# loiterboard.net
KiCad netlist of a schematic drawn in EAGLE
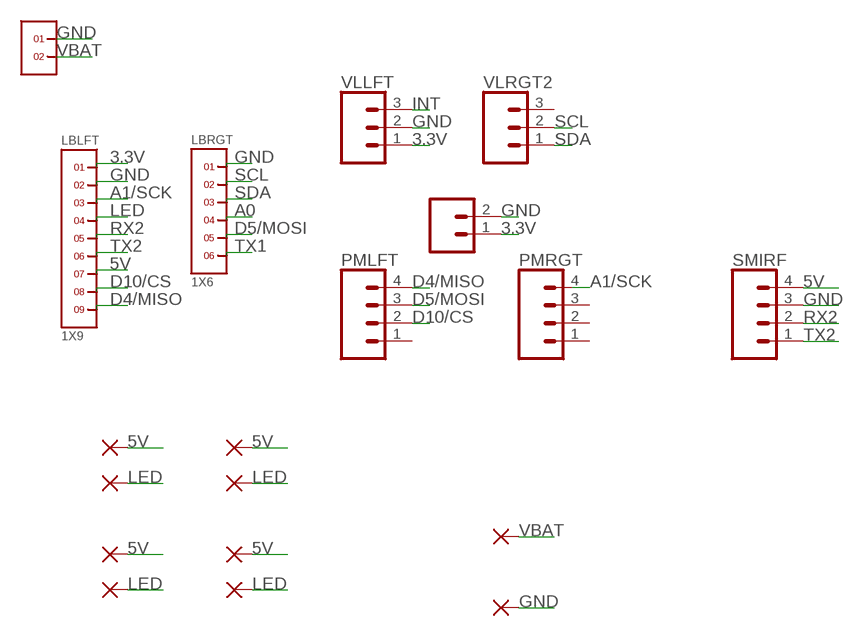
[diagram p0: schematic, sheet 1]

(export (version "E")
  (design (tool "Eeschema 10.0.6"))
  (components
    (comp (ref "LBLFT")
      (value "1X9")
      (footprint "eagle-import:1X9")
      (libsource (lib "eagle-import") (part "1X9"))
    )
    (comp (ref "LBRGT")
      (value "1X6")
      (footprint "eagle-import:1X6")
      (libsource (lib "eagle-import") (part "1X6"))
    )
    (comp (ref "PAD1")
      (value "SMD2")
      (footprint "eagle-import:SMD1,27-2,54")
      (libsource (lib "eagle-import") (part "SMD2"))
    )
    (comp (ref "PAD2")
      (value "SMD2")
      (footprint "eagle-import:SMD1,27-2,54")
      (libsource (lib "eagle-import") (part "SMD2"))
    )
    (comp (ref "PAD3")
      (value "SMD2")
      (footprint "eagle-import:SMD1,27-2,54")
      (libsource (lib "eagle-import") (part "SMD2"))
    )
    (comp (ref "PAD4")
      (value "SMD2")
      (footprint "eagle-import:SMD1,27-2,54")
      (libsource (lib "eagle-import") (part "SMD2"))
    )
    (comp (ref "PAD5")
      (value "SMD2")
      (footprint "eagle-import:SMD1,27-2,54")
      (libsource (lib "eagle-import") (part "SMD2"))
    )
    (comp (ref "PAD6")
      (value "LED")
      (footprint "eagle-import:SMD1,27-2,54")
      (libsource (lib "eagle-import") (part "SMD2"))
    )
    (comp (ref "PAD7")
      (value "SMD2")
      (footprint "eagle-import:SMD1,27-2,54")
      (libsource (lib "eagle-import") (part "SMD2"))
    )
    (comp (ref "PAD8")
      (value "SMD2")
      (footprint "eagle-import:SMD1,27-2,54")
      (libsource (lib "eagle-import") (part "SMD2"))
    )
    (comp (ref "PAD9")
      (value "SMD2")
      (footprint "eagle-import:SMD1,27-2,54")
      (libsource (lib "eagle-import") (part "SMD2"))
    )
    (comp (ref "PAD10")
      (value "SMD2")
      (footprint "eagle-import:SMD1,27-2,54")
      (libsource (lib "eagle-import") (part "SMD2"))
    )
    (comp (ref "PMLFT")
      (value "CONN_04")
      (footprint "eagle-import:1X04")
      (libsource (lib "eagle-import") (part "CONN_04"))
    )
    (comp (ref "PMRGT")
      (value "CONN_04")
      (footprint "eagle-import:1X04")
      (libsource (lib "eagle-import") (part "CONN_04"))
    )
    (comp (ref "PWPWR")
      (value "CONN_02")
      (footprint "eagle-import:1X02")
      (libsource (lib "eagle-import") (part "CONN_02"))
    )
    (comp (ref "SMIRF")
      (value "CONN_04")
      (footprint "eagle-import:1X04")
      (libsource (lib "eagle-import") (part "CONN_04"))
    )
    (comp (ref "U$1")
      (value "1X2")
      (footprint "eagle-import:1X2")
      (libsource (lib "eagle-import") (part "1X2"))
    )
    (comp (ref "VLLFT")
      (value "CONN_03")
      (footprint "eagle-import:1X03")
      (libsource (lib "eagle-import") (part "CONN_03"))
    )
    (comp (ref "VLRGT2")
      (value "CONN_03")
      (footprint "eagle-import:1X03")
      (libsource (lib "eagle-import") (part "CONN_03"))
    )
  )
  (nets
    (net (code "1") (name "/3.3V") (class "Default")
      (node (ref "LBLFT") (pin "1") (pinfunction "1_1") (pintype "bidirectional"))
      (node (ref "PWPWR") (pin "1") (pinfunction "1_1") (pintype "passive"))
      (node (ref "VLLFT") (pin "1") (pinfunction "1_1") (pintype "passive"))
    )
    (net (code "2") (name "/5V") (class "Default")
      (node (ref "LBLFT") (pin "7") (pinfunction "7_7") (pintype "bidirectional"))
      (node (ref "PAD1") (pin "1") (pinfunction "P_1") (pintype "passive"))
      (node (ref "PAD3") (pin "1") (pinfunction "P_1") (pintype "passive"))
      (node (ref "PAD5") (pin "1") (pinfunction "P_1") (pintype "passive"))
      (node (ref "PAD7") (pin "1") (pinfunction "P_1") (pintype "passive"))
      (node (ref "SMIRF") (pin "4") (pinfunction "4_4") (pintype "passive"))
    )
    (net (code "3") (name "/A0") (class "Default")
      (node (ref "LBRGT") (pin "4") (pinfunction "4_4") (pintype "bidirectional"))
    )
    (net (code "4") (name "/A1{slash}SCK") (class "Default")
      (node (ref "LBLFT") (pin "3") (pinfunction "3_3") (pintype "bidirectional"))
      (node (ref "PMRGT") (pin "4") (pinfunction "4_4") (pintype "passive"))
    )
    (net (code "5") (name "/D4{slash}MISO") (class "Default")
      (node (ref "LBLFT") (pin "9") (pinfunction "9_9") (pintype "bidirectional"))
      (node (ref "PMLFT") (pin "4") (pinfunction "4_4") (pintype "passive"))
    )
    (net (code "6") (name "/D5{slash}MOSI") (class "Default")
      (node (ref "LBRGT") (pin "5") (pinfunction "5_5") (pintype "bidirectional"))
      (node (ref "PMLFT") (pin "3") (pinfunction "3_3") (pintype "passive"))
    )
    (net (code "7") (name "/D10{slash}CS") (class "Default")
      (node (ref "LBLFT") (pin "8") (pinfunction "8_8") (pintype "bidirectional"))
      (node (ref "PMLFT") (pin "2") (pinfunction "2_2") (pintype "passive"))
    )
    (net (code "8") (name "/GND") (class "Default")
      (node (ref "LBLFT") (pin "2") (pinfunction "2_2") (pintype "bidirectional"))
      (node (ref "LBRGT") (pin "1") (pinfunction "1_1") (pintype "bidirectional"))
      (node (ref "PAD10") (pin "1") (pinfunction "P_1") (pintype "passive"))
      (node (ref "PWPWR") (pin "2") (pinfunction "2_2") (pintype "passive"))
      (node (ref "SMIRF") (pin "3") (pinfunction "3_3") (pintype "passive"))
      (node (ref "U$1") (pin "1") (pinfunction "1_1") (pintype "bidirectional"))
      (node (ref "VLLFT") (pin "2") (pinfunction "2_2") (pintype "passive"))
    )
    (net (code "9") (name "/INT") (class "Default")
      (node (ref "VLLFT") (pin "3") (pinfunction "3_3") (pintype "passive"))
    )
    (net (code "10") (name "/LED") (class "Default")
      (node (ref "LBLFT") (pin "4") (pinfunction "4_4") (pintype "bidirectional"))
      (node (ref "PAD2") (pin "1") (pinfunction "P_1") (pintype "passive"))
      (node (ref "PAD4") (pin "1") (pinfunction "P_1") (pintype "passive"))
      (node (ref "PAD6") (pin "1") (pinfunction "P_1") (pintype "passive"))
      (node (ref "PAD8") (pin "1") (pinfunction "P_1") (pintype "passive"))
    )
    (net (code "11") (name "/RX2") (class "Default")
      (node (ref "LBLFT") (pin "5") (pinfunction "5_5") (pintype "bidirectional"))
      (node (ref "SMIRF") (pin "2") (pinfunction "2_2") (pintype "passive"))
    )
    (net (code "12") (name "/SCL") (class "Default")
      (node (ref "LBRGT") (pin "2") (pinfunction "2_2") (pintype "bidirectional"))
      (node (ref "VLRGT2") (pin "2") (pinfunction "2_2") (pintype "passive"))
    )
    (net (code "13") (name "/SDA") (class "Default")
      (node (ref "LBRGT") (pin "3") (pinfunction "3_3") (pintype "bidirectional"))
      (node (ref "VLRGT2") (pin "1") (pinfunction "1_1") (pintype "passive"))
    )
    (net (code "14") (name "/TX1") (class "Default")
      (node (ref "LBRGT") (pin "6") (pinfunction "6_6") (pintype "bidirectional"))
    )
    (net (code "15") (name "/TX2") (class "Default")
      (node (ref "LBLFT") (pin "6") (pinfunction "6_6") (pintype "bidirectional"))
      (node (ref "SMIRF") (pin "1") (pinfunction "1_1") (pintype "passive"))
    )
    (net (code "16") (name "/VBAT") (class "Default")
      (node (ref "PAD9") (pin "1") (pinfunction "P_1") (pintype "passive"))
      (node (ref "U$1") (pin "2") (pinfunction "2_2") (pintype "bidirectional"))
    )
    (net (code "17") (name "unconnected-(PMLFT-Pad1)") (class "Default")
      (node (ref "PMLFT") (pin "1") (pinfunction "1_1") (pintype "passive"))
    )
    (net (code "18") (name "unconnected-(PMRGT-Pad1)") (class "Default")
      (node (ref "PMRGT") (pin "1") (pinfunction "1_1") (pintype "passive"))
    )
    (net (code "19") (name "unconnected-(PMRGT-Pad2)") (class "Default")
      (node (ref "PMRGT") (pin "2") (pinfunction "2_2") (pintype "passive"))
    )
    (net (code "20") (name "unconnected-(PMRGT-Pad3)") (class "Default")
      (node (ref "PMRGT") (pin "3") (pinfunction "3_3") (pintype "passive"))
    )
    (net (code "21") (name "unconnected-(VLRGT2-Pad3)") (class "Default")
      (node (ref "VLRGT2") (pin "3") (pinfunction "3_3") (pintype "passive"))
    )
  )
)
